# COM-Radio-UHF.net
KiCad netlist of a schematic drawn in Altium Designer
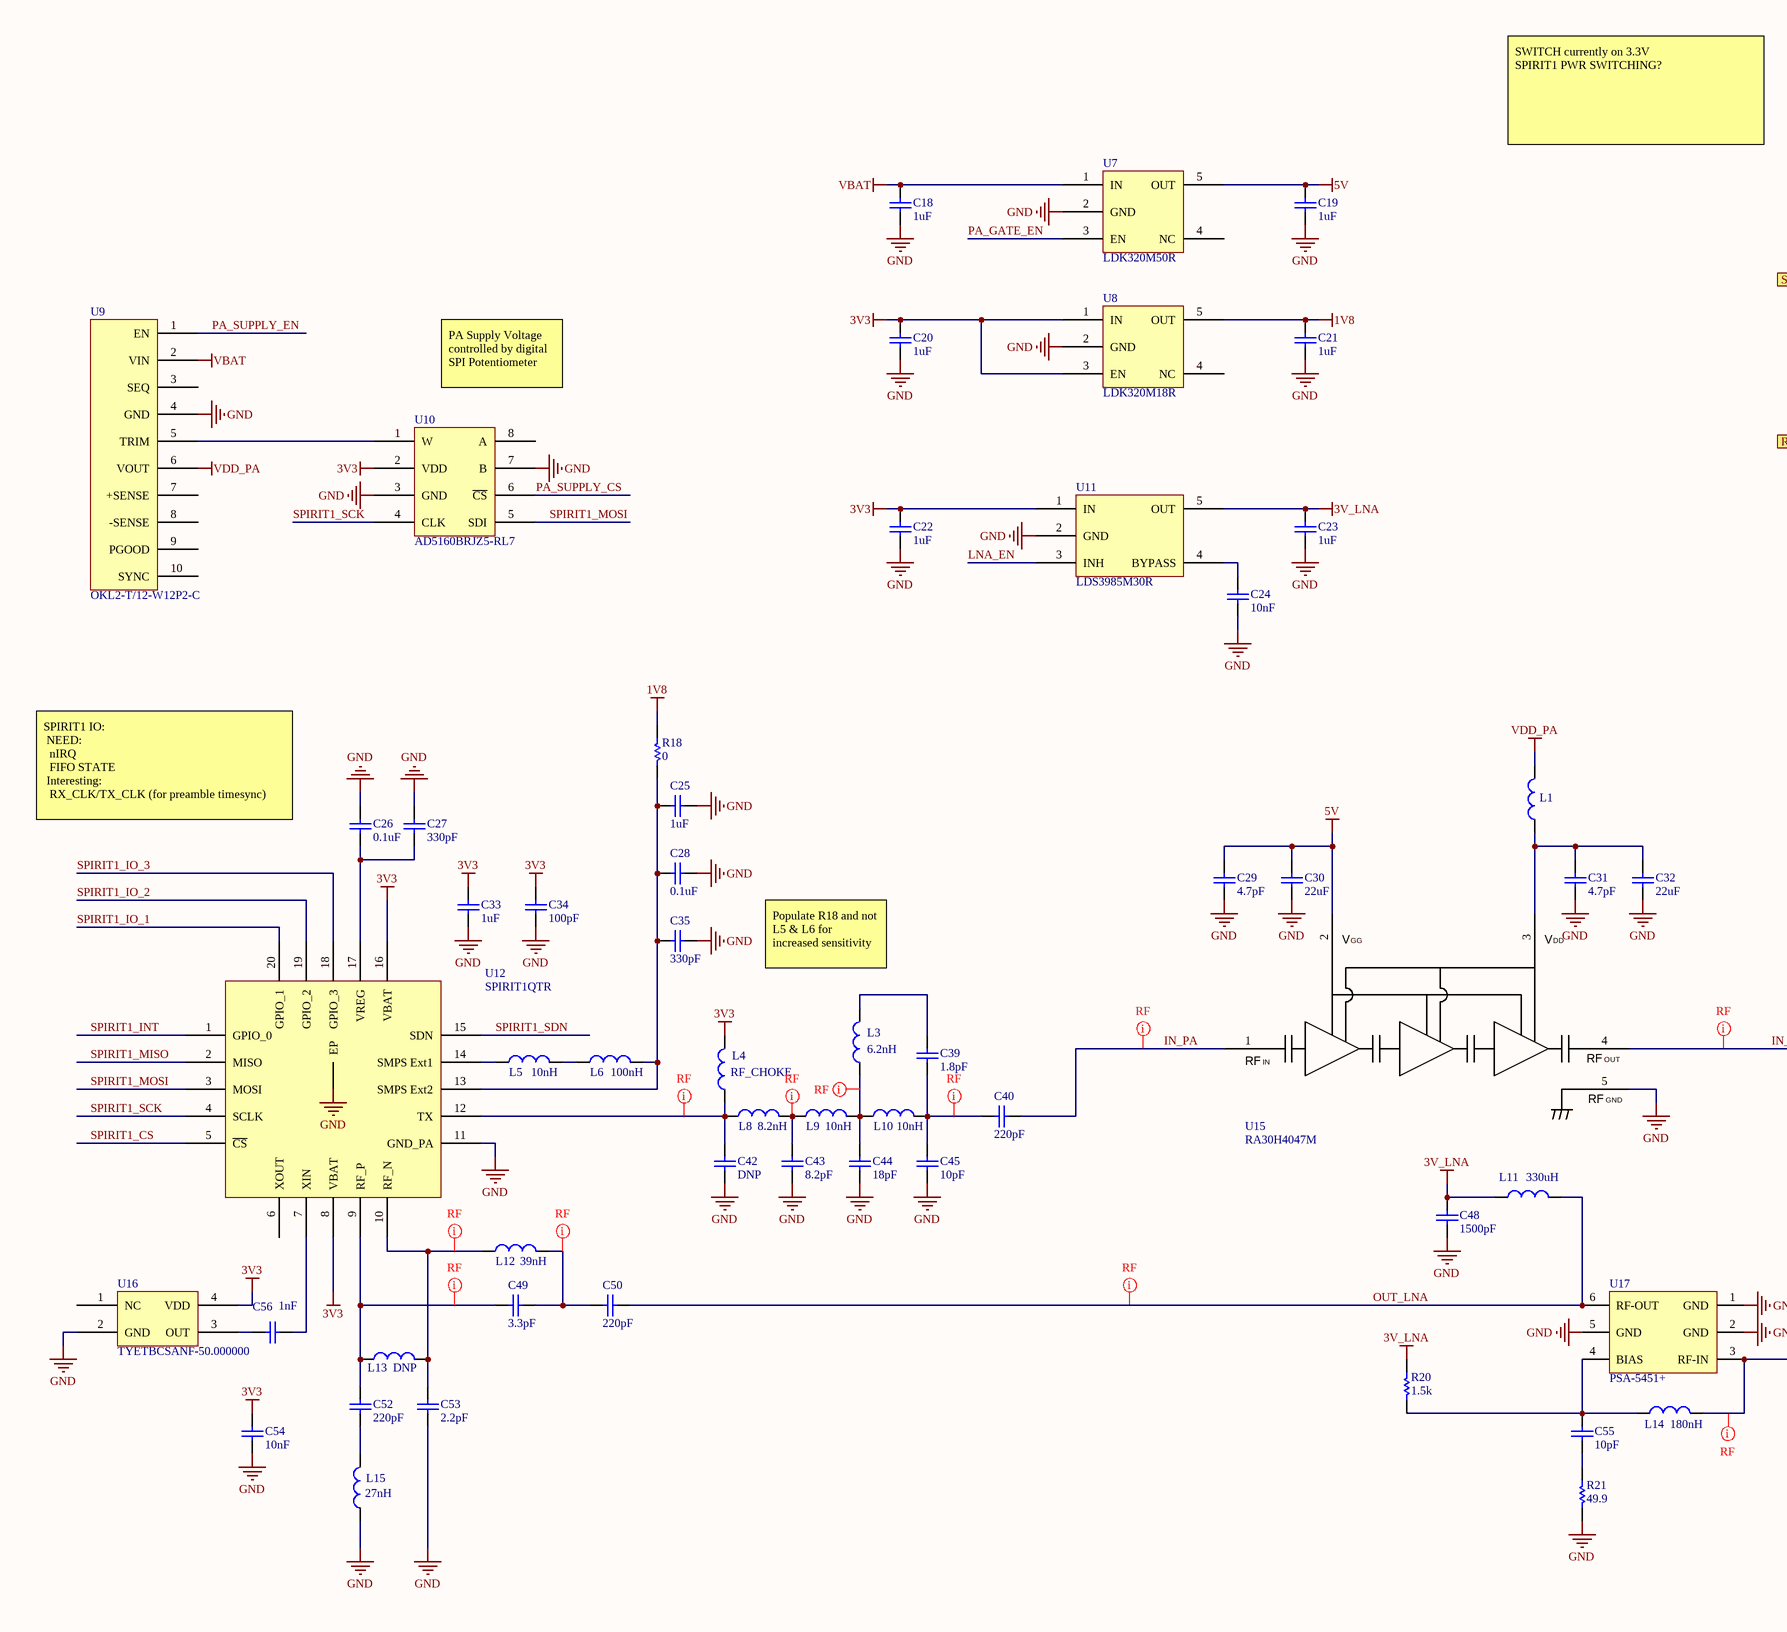
[diagram p0: COM-Radio-UHF.SchDoc, left]
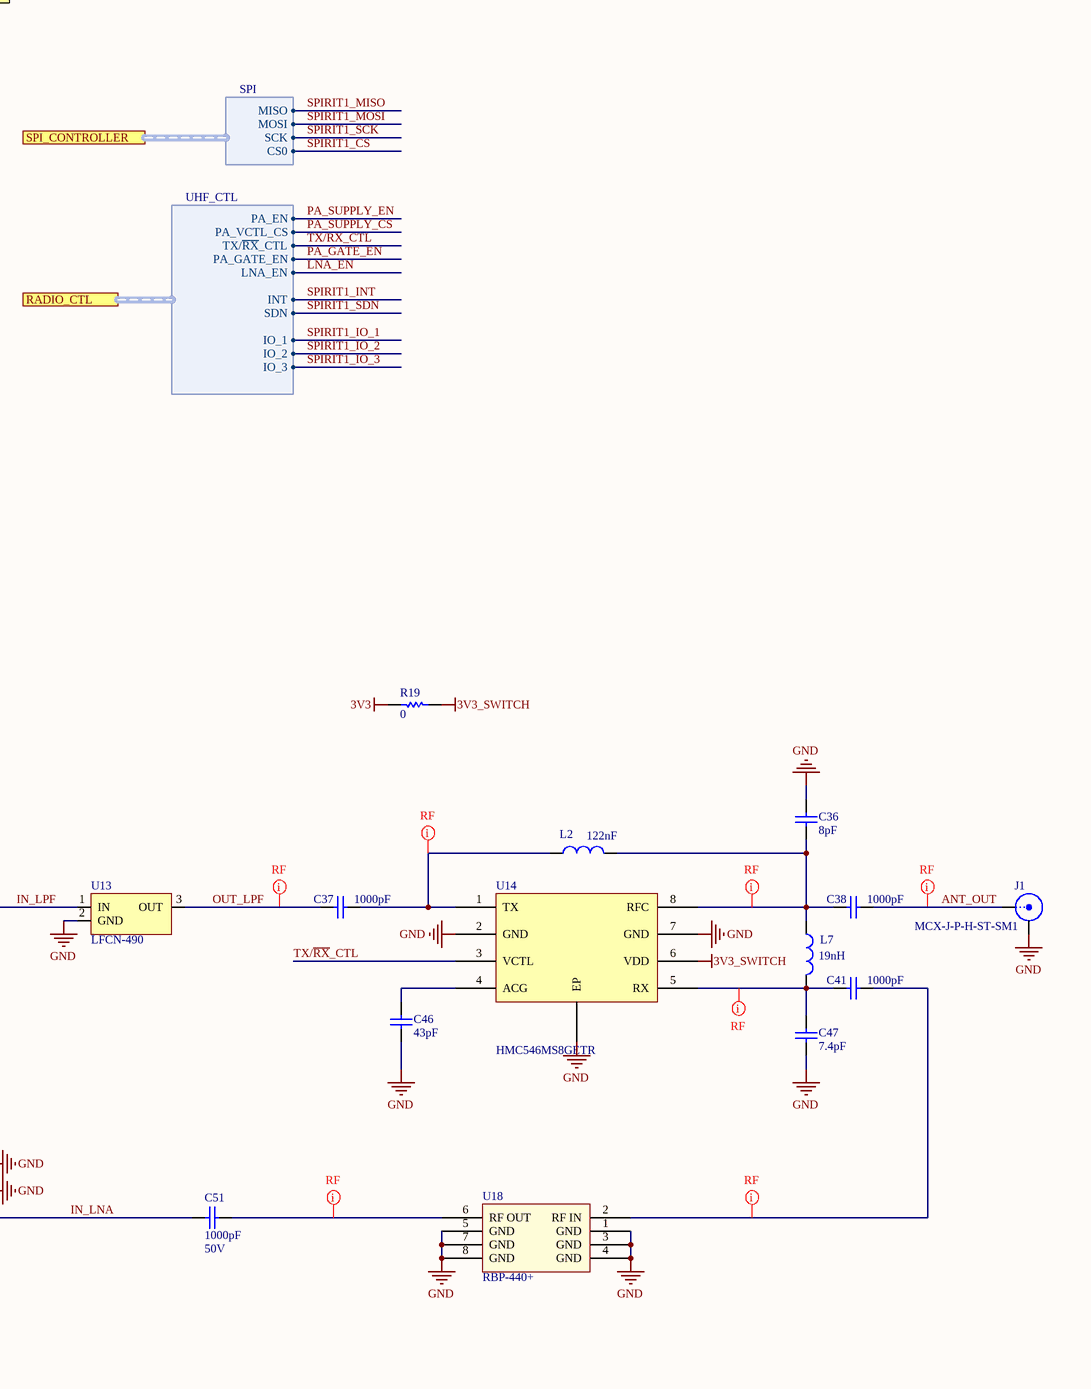
[diagram p1: COM-Radio-UHF.SchDoc, right]

(export (version "E")
  (design (tool "Eeschema 10.0.6"))
  (components
    (comp (ref "C18")
      (value "CL10B105MO8NNWC")
      (footprint "1608[0603]")
      (description "CAP CER 1UF 16V X7R 0603")
      (fields
        (field (name "CAPACITANCE") "1uF")
        (field (name "PARTNUMBER") "CGA2B2X7R1H102M050BA")
        (field (name "MANUFACTURER") "TDK")
      )
      (libsource (lib "PolarCube") (part "Cap"))
    )
    (comp (ref "C19")
      (value "CL10B105MO8NNWC")
      (footprint "1608[0603]")
      (description "CAP CER 1UF 16V X7R 0603")
      (fields
        (field (name "CAPACITANCE") "1uF")
        (field (name "PARTNUMBER") "CGA2B2X7R1H102M050BA")
        (field (name "MANUFACTURER") "TDK")
      )
      (libsource (lib "PolarCube") (part "Cap"))
    )
    (comp (ref "C20")
      (value "CL10B105MO8NNWC")
      (footprint "1608[0603]")
      (description "CAP CER 1UF 16V X7R 0603")
      (fields
        (field (name "CAPACITANCE") "1uF")
        (field (name "PARTNUMBER") "CGA2B2X7R1H102M050BA")
        (field (name "MANUFACTURER") "TDK")
      )
      (libsource (lib "PolarCube") (part "Cap"))
    )
    (comp (ref "C21")
      (value "CL10B105MO8NNWC")
      (footprint "1608[0603]")
      (description "CAP CER 1UF 16V X7R 0603")
      (fields
        (field (name "CAPACITANCE") "1uF")
        (field (name "PARTNUMBER") "CGA2B2X7R1H102M050BA")
        (field (name "MANUFACTURER") "TDK")
      )
      (libsource (lib "PolarCube") (part "Cap"))
    )
    (comp (ref "C22")
      (value "CL10B105MO8NNWC")
      (footprint "1608[0603]")
      (description "CAP CER 1UF 16V X7R 0603")
      (fields
        (field (name "CAPACITANCE") "1uF")
        (field (name "PARTNUMBER") "CGA2B2X7R1H102M050BA")
        (field (name "MANUFACTURER") "TDK")
      )
      (libsource (lib "PolarCube") (part "Cap"))
    )
    (comp (ref "C23")
      (value "CL10B105MO8NNWC")
      (footprint "1608[0603]")
      (description "CAP CER 1UF 16V X7R 0603")
      (fields
        (field (name "CAPACITANCE") "1uF")
        (field (name "PARTNUMBER") "CGA2B2X7R1H102M050BA")
        (field (name "MANUFACTURER") "TDK")
      )
      (libsource (lib "PolarCube") (part "Cap"))
    )
    (comp (ref "C24")
      (value "CL10B103KO8NNNC")
      (footprint "1608[0603]")
      (description "CAP CER 10000PF 16V X7R 0603")
      (fields
        (field (name "CAPACITANCE") "10nF")
        (field (name "PARTNUMBER") "CGA2B2X7R1H102M050BA")
        (field (name "MANUFACTURER") "TDK")
      )
      (libsource (lib "PolarCube") (part "Cap"))
    )
    (comp (ref "C25")
      (value "CL10B105MO8NNWC")
      (footprint "1608[0603]")
      (description "CAP CER 1UF 16V X7R 0603")
      (fields
        (field (name "CAPACITANCE") "1uF")
        (field (name "PARTNUMBER") "CBR04C100J5GAC")
        (field (name "MANUFACTURER") "Kemet")
      )
      (libsource (lib "PolarCube") (part "Cap"))
    )
    (comp (ref "C26")
      (value "CL10B104KB8ZW6C")
      (footprint "1608[0603]")
      (description "MLCC 1608(0603) X7R 100NF 10% 50")
      (fields
        (field (name "CAPACITANCE") "0.1uF")
        (field (name "PARTNUMBER") "CBR04C100J5GAC")
        (field (name "MANUFACTURER") "Kemet")
      )
      (libsource (lib "PolarCube") (part "Cap"))
    )
    (comp (ref "C27")
      (value "CL10C331JB8NFNC")
      (footprint "1608[0603]")
      (description "CAP CER 330PF 50V C0G/NP0 0603")
      (fields
        (field (name "CAPACITANCE") "330pF")
        (field (name "PARTNUMBER") "CBR04C100J5GAC")
        (field (name "MANUFACTURER") "Kemet")
      )
      (libsource (lib "PolarCube") (part "Cap"))
    )
    (comp (ref "C28")
      (value "CL10B104KB8ZW6C")
      (footprint "1608[0603]")
      (description "MLCC 1608(0603) X7R 100NF 10% 50")
      (fields
        (field (name "CAPACITANCE") "0.1uF")
        (field (name "PARTNUMBER") "CBR04C100J5GAC")
        (field (name "MANUFACTURER") "Kemet")
      )
      (libsource (lib "PolarCube") (part "Cap"))
    )
    (comp (ref "C29")
      (value "CL10C4R7BB8NNNC")
      (footprint "1608[0603]")
      (description "CAP CER 4.7PF 50V C0G/NP0 0603")
      (fields
        (field (name "CAPACITANCE") "4.7pF")
        (field (name "PARTNUMBER") "CGA2B2X7R1H102M050BA")
        (field (name "MANUFACTURER") "TDK")
      )
      (libsource (lib "PolarCube") (part "Cap"))
    )
    (comp (ref "C30")
      (value "C3225X5R1C226M250AA")
      (footprint "C1210_M")
      (description "CAP CER 22UF 16V X5R 1210")
      (fields
        (field (name "CAPACITANCE") "22uF")
        (field (name "PARTNUMBER") "CGA2B2X7R1H102M050BA")
        (field (name "MANUFACTURER") "TDK")
      )
      (libsource (lib "PolarCube") (part "Cap"))
    )
    (comp (ref "C31")
      (value "CL10C4R7BB8NNNC")
      (footprint "1608[0603]")
      (description "CAP CER 4.7PF 50V C0G/NP0 0603")
      (fields
        (field (name "CAPACITANCE") "4.7pF")
        (field (name "PARTNUMBER") "CGA2B2X7R1H102M050BA")
        (field (name "MANUFACTURER") "TDK")
      )
      (libsource (lib "PolarCube") (part "Cap"))
    )
    (comp (ref "C32")
      (value "C3225X5R1C226M250AA")
      (footprint "C1210_M")
      (description "CAP CER 22UF 16V X5R 1210")
      (fields
        (field (name "CAPACITANCE") "22uF")
        (field (name "PARTNUMBER") "CGA2B2X7R1H102M050BA")
        (field (name "MANUFACTURER") "TDK")
      )
      (libsource (lib "PolarCube") (part "Cap"))
    )
    (comp (ref "C33")
      (value "CL10B105MO8NNWC")
      (footprint "1608[0603]")
      (description "CAP CER 1UF 16V X7R 0603")
      (fields
        (field (name "CAPACITANCE") "1uF")
        (field (name "PARTNUMBER") "CBR04C100J5GAC")
        (field (name "MANUFACTURER") "Kemet")
      )
      (libsource (lib "PolarCube") (part "Cap"))
    )
    (comp (ref "C34")
      (value "C0603C101K5GACTU")
      (footprint "1608[0603]")
      (description "CAP CER 100PF 50V C0G/NP0 0603")
      (fields
        (field (name "CAPACITANCE") "100pF")
        (field (name "PARTNUMBER") "CBR04C100J5GAC")
        (field (name "MANUFACTURER") "Kemet")
      )
      (libsource (lib "PolarCube") (part "Cap"))
    )
    (comp (ref "C35")
      (value "CL10B331JB8NNNC")
      (footprint "1608[0603]")
      (description "CAP CER 330PF 50V X7R 0603")
      (fields
        (field (name "CAPACITANCE") "330pF")
        (field (name "PARTNUMBER") "CBR04C100J5GAC")
        (field (name "MANUFACTURER") "Kemet")
      )
      (libsource (lib "PolarCube") (part "Cap"))
    )
    (comp (ref "C36")
      (value "CL10C080CB8NNNC")
      (footprint "1608[0603]")
      (description "CAP CER 8PF 50V C0G/NP0 0603")
      (fields
        (field (name "CAPACITANCE") "8pF")
        (field (name "PARTNUMBER") "CGA2B2X7R1H102M050BA")
        (field (name "MANUFACTURER") "TDK")
      )
      (libsource (lib "PolarCube") (part "Cap"))
    )
    (comp (ref "C37")
      (value "C0603X102J5GAC7867")
      (footprint "1608[0603]")
      (description "CAP CER 1000PF 50V C0G/NP0 0603")
      (fields
        (field (name "CAPACITANCE") "1000pF")
        (field (name "PARTNUMBER") "CGA2B2X7R1H102M050BA")
        (field (name "MANUFACTURER") "TDK")
      )
      (libsource (lib "PolarCube") (part "Cap"))
    )
    (comp (ref "C38")
      (value "C0603X102J5GAC7867")
      (footprint "1608[0603]")
      (description "CAP CER 1000PF 50V C0G/NP0 0603")
      (fields
        (field (name "CAPACITANCE") "1000pF")
        (field (name "PARTNUMBER") "CGA2B2X7R1H102M050BA")
        (field (name "MANUFACTURER") "TDK")
      )
      (libsource (lib "PolarCube") (part "Cap"))
    )
    (comp (ref "C39")
      (value "CL10C1R8BB8NNNC")
      (footprint "1608[0603]")
      (description "CAP CER 1.8PF 50V C0G/NP0 0603")
      (fields
        (field (name "CAPACITANCE") "1.8pF")
        (field (name "PARTNUMBER") "CBR04C100J5GAC")
        (field (name "MANUFACTURER") "Kemet")
      )
      (libsource (lib "PolarCube") (part "Cap"))
    )
    (comp (ref "C40")
      (value "CL10C221JB8NNNC")
      (footprint "1608[0603]")
      (description "CAP CER 220PF 50V C0G/NP0 0603")
      (fields
        (field (name "CAPACITANCE") "220pF")
        (field (name "PARTNUMBER") "CBR04C100J5GAC")
        (field (name "MANUFACTURER") "Kemet")
      )
      (libsource (lib "PolarCube") (part "Cap"))
    )
    (comp (ref "C41")
      (value "C0603X102J5GAC7867")
      (footprint "1608[0603]")
      (description "CAP CER 1000PF 50V C0G/NP0 0603")
      (fields
        (field (name "CAPACITANCE") "1000pF")
        (field (name "PARTNUMBER") "CGA2B2X7R1H102M050BA")
        (field (name "MANUFACTURER") "TDK")
      )
      (libsource (lib "PolarCube") (part "Cap"))
    )
    (comp (ref "C42")
      (value "Cap")
      (footprint "1608[0603]")
      (description "RF Microwave MLCCs")
      (fields
        (field (name "CAPACITANCE") "DNP")
        (field (name "PARTNUMBER") "CBR04C100J5GAC")
        (field (name "MANUFACTURER") "Kemet")
      )
      (libsource (lib "PolarCube") (part "Cap"))
    )
    (comp (ref "C43")
      (value "CL10C8R2DB8NNNC")
      (footprint "1608[0603]")
      (description "CAP CER 8.2PF 50V C0G/NP0 0603")
      (fields
        (field (name "CAPACITANCE") "8.2pF")
        (field (name "PARTNUMBER") "CBR04C100J5GAC")
        (field (name "MANUFACTURER") "Kemet")
      )
      (libsource (lib "PolarCube") (part "Cap"))
    )
    (comp (ref "C44")
      (value "C0603C180K5GACTU")
      (footprint "1608[0603]")
      (description "CAP CER 18PF 50V C0G/NP0 0603")
      (fields
        (field (name "CAPACITANCE") "18pF")
        (field (name "PARTNUMBER") "CBR04C100J5GAC")
        (field (name "MANUFACTURER") "Kemet")
      )
      (libsource (lib "PolarCube") (part "Cap"))
    )
    (comp (ref "C45")
      (value "CL10C100JB8NCNC")
      (footprint "1608[0603]")
      (description "CAP CER 10PF 50V C0G/NP0 0603")
      (fields
        (field (name "CAPACITANCE") "10pF")
        (field (name "PARTNUMBER") "CBR04C100J5GAC")
        (field (name "MANUFACTURER") "Kemet")
      )
      (libsource (lib "PolarCube") (part "Cap"))
    )
    (comp (ref "C46")
      (value "C0603C430J5GACTU")
      (footprint "1608[0603]")
      (description "CAP CER 43PF 50V C0G/NP0 0603")
      (fields
        (field (name "CAPACITANCE") "43pF")
        (field (name "PARTNUMBER") "CGA2B2X7R1H102M050BA")
        (field (name "MANUFACTURER") "TDK")
      )
      (libsource (lib "PolarCube") (part "Cap"))
    )
    (comp (ref "C47")
      (value "CBR06C749B5GAC")
      (footprint "1608[0603]")
      (description "CAP CER RF 7.4PF 50V +/-0.1 PF C")
      (fields
        (field (name "CAPACITANCE") "7.4pF")
        (field (name "PARTNUMBER") "CGA2B2X7R1H102M050BA")
        (field (name "MANUFACTURER") "TDK")
      )
      (libsource (lib "PolarCube") (part "Cap"))
    )
    (comp (ref "C48")
      (value "C0603C152J5GACTU")
      (footprint "1608[0603]")
      (description "CAP CER 1500PF 50V C0G/NP0 0603")
      (fields
        (field (name "CAPACITANCE") "1500pF")
        (field (name "PARTNUMBER") "CGA2B2X7R1H102M050BA")
        (field (name "MANUFACTURER") "TDK")
      )
      (libsource (lib "PolarCube") (part "Cap"))
    )
    (comp (ref "C49")
      (value "06035A3R3BAT2A")
      (footprint "1608[0603]")
      (description "CAP CER 3.3PF 50V C0G/NP0 0603")
      (fields
        (field (name "CAPACITANCE") "3.3pF")
        (field (name "PARTNUMBER") "CBR04C100J5GAC")
        (field (name "MANUFACTURER") "Kemet")
      )
      (libsource (lib "PolarCube") (part "Cap"))
    )
    (comp (ref "C50")
      (value "CL10C221JB8NNNC")
      (footprint "1608[0603]")
      (description "CAP CER 220PF 50V C0G/NP0 0603")
      (fields
        (field (name "CAPACITANCE") "220pF")
        (field (name "PARTNUMBER") "CBR04C100J5GAC")
        (field (name "MANUFACTURER") "Kemet")
      )
      (libsource (lib "PolarCube") (part "Cap"))
    )
    (comp (ref "C51")
      (value "C0603X102J5GAC7867")
      (footprint "1608[0603]")
      (description "CAP CER 1000PF 50V C0G/NP0 0603")
      (fields
        (field (name "CAPACITANCE") "1000pF")
        (field (name "VOLTAGE") "50V")
        (field (name "PARTNUMBER") "CGA2B2X7R1H102M050BA")
        (field (name "MANUFACTURER") "TDK")
      )
      (libsource (lib "PolarCube") (part "Cap"))
    )
    (comp (ref "C52")
      (value "CL10C221JB8NNNC")
      (footprint "1608[0603]")
      (description "CAP CER 220PF 50V C0G/NP0 0603")
      (fields
        (field (name "CAPACITANCE") "220pF")
        (field (name "PARTNUMBER") "CBR04C100J5GAC")
        (field (name "MANUFACTURER") "Kemet")
      )
      (libsource (lib "PolarCube") (part "Cap"))
    )
    (comp (ref "C53")
      (value "C0603C229B5GAC7867")
      (footprint "1608[0603]")
      (description "CAP CER 2.2PF 50V NP0 0603")
      (fields
        (field (name "CAPACITANCE") "2.2pF")
        (field (name "PARTNUMBER") "CBR04C100J5GAC")
        (field (name "MANUFACTURER") "Kemet")
      )
      (libsource (lib "PolarCube") (part "Cap"))
    )
    (comp (ref "C54")
      (value "Cap")
      (footprint "1608[0603]")
      (description "RF Microwave MLCCs")
      (fields
        (field (name "CAPACITANCE") "10nF")
        (field (name "PARTNUMBER") "CBR04C100J5GAC")
        (field (name "MANUFACTURER") "Kemet")
      )
      (libsource (lib "PolarCube") (part "Cap"))
    )
    (comp (ref "C55")
      (value "CL10C100JB8NCNC")
      (footprint "1608[0603]")
      (description "CAP CER 10PF 50V C0G/NP0 0603")
      (fields
        (field (name "CAPACITANCE") "10pF")
        (field (name "PARTNUMBER") "CBR04C100J5GAC")
        (field (name "MANUFACTURER") "Kemet")
      )
      (libsource (lib "PolarCube") (part "Cap"))
    )
    (comp (ref "C56")
      (value "CL10B102KA8NNNC")
      (footprint "1608[0603]")
      (description "CAP CER 1000PF 25V X7R 0603")
      (fields
        (field (name "CAPACITANCE") "1nF")
        (field (name "PARTNUMBER") "CBR04C100J5GAC")
        (field (name "MANUFACTURER") "Kemet")
      )
      (libsource (lib "PolarCube") (part "Cap"))
    )
    (comp (ref "J1")
      (value "MCX-J-P-H-ST-SM1")
      (footprint "MCX-J-P-H-ST-SM1")
      (description "MCX Connector Jack, Female Socket 50 Ohm Surface Mount Solder")
      (fields (field (name "PARTNUMBER") "MMCX-J-P-H-RA-TH1"))
      (libsource (lib "UHF-schlib") (part "MMCX-J-P-H-RA-TH1"))
    )
    (comp (ref "L1")
      (value "SDR2207-4R7ML")
      (footprint "SDR2207-4R7ML")
      (description "FIXED IND 4.7UH 8.5A 8.8 MOHM")
      (fields (field (name "PARTNUMBER") "MLG1005SR18JT000") (field (name "MANUFACTURER") "TDK"))
      (libsource (lib "PolarCube") (part "Inductor"))
    )
    (comp (ref "L2")
      (value "PE-0603CD121GTT")
      (footprint "1608[0603]")
      (description "FIXED IND 122NH 300MA 650 MOHM")
      (fields
        (field (name "INDUCTANCE") "122nF")
        (field (name "PARTNUMBER") "MLG1005SR18JT000")
        (field (name "MANUFACTURER") "TDK")
      )
      (libsource (lib "PolarCube") (part "Inductor"))
    )
    (comp (ref "L3")
      (value "LQG18HH6N2S00D")
      (footprint "1608[0603]")
      (description "FIXED IND 6.2NH 430MA 200 MOHM")
      (fields
        (field (name "INDUCTANCE") "6.2nH")
        (field (name "PARTNUMBER") "MLG1005SR18JT000")
        (field (name "MANUFACTURER") "TDK")
      )
      (libsource (lib "PolarCube") (part "Inductor"))
    )
    (comp (ref "L4")
      (value "LQM21FN100M80L")
      (footprint "6-0805_M")
      (description "FIXED IND 10UH 100MA 300 MOHM")
      (fields
        (field (name "PARTNUMBER") "MLG1005SR18JT000")
        (field (name "MANUFACTURER") "TDK")
        (field (name "TYPE") "RF_CHOKE")
      )
      (libsource (lib "PolarCube") (part "Inductor"))
    )
    (comp (ref "L5")
      (value "L-14C10NJV4T")
      (footprint "1608[0603]")
      (description "FIXED IND 10NH 300MA 350 MOHM")
      (fields
        (field (name "INDUCTANCE") "10nH")
        (field (name "PARTNUMBER") "MLG1005SR18JT000")
        (field (name "MANUFACTURER") "TDK")
      )
      (libsource (lib "PolarCube") (part "Inductor"))
    )
    (comp (ref "L6")
      (value "HK1608R10J-T")
      (footprint "1608[0603]")
      (description "FIXED IND 100NH 300MA 100 MOHM")
      (fields
        (field (name "INDUCTANCE") "100nH")
        (field (name "PARTNUMBER") "MLG1005SR18JT000")
        (field (name "MANUFACTURER") "TDK")
      )
      (libsource (lib "PolarCube") (part "Inductor"))
    )
    (comp (ref "L7")
      (value "LQW18AN19NJ8ZD")
      (footprint "1608[0603]")
      (description "FIXED IND 19NH 1.4A 75 MOHM")
      (fields
        (field (name "INDUCTANCE") "19nH")
        (field (name "PARTNUMBER") "MLG1005SR18JT000")
        (field (name "MANUFACTURER") "TDK")
      )
      (libsource (lib "PolarCube") (part "Inductor"))
    )
    (comp (ref "L8")
      (value "L-14C8N2JV4T")
      (footprint "1608[0603]")
      (description "FIXED IND 8.2NH 300MA 330 MOHM")
      (fields
        (field (name "INDUCTANCE") "8.2nH")
        (field (name "PARTNUMBER") "MLG1005SR18JT000")
        (field (name "MANUFACTURER") "TDK")
      )
      (libsource (lib "PolarCube") (part "Inductor"))
    )
    (comp (ref "L9")
      (value "L-14C10NJV4T")
      (footprint "1608[0603]")
      (description "FIXED IND 10NH 300MA 350 MOHM")
      (fields
        (field (name "INDUCTANCE") "10nH")
        (field (name "PARTNUMBER") "MLG1005SR18JT000")
        (field (name "MANUFACTURER") "TDK")
      )
      (libsource (lib "PolarCube") (part "Inductor"))
    )
    (comp (ref "L10")
      (value "L-14C10NJV4T")
      (footprint "1608[0603]")
      (description "FIXED IND 10NH 300MA 350 MOHM")
      (fields
        (field (name "INDUCTANCE") "10nH")
        (field (name "PARTNUMBER") "MLG1005SR18JT000")
        (field (name "MANUFACTURER") "TDK")
      )
      (libsource (lib "PolarCube") (part "Inductor"))
    )
    (comp (ref "L11")
      (value "SRR7045-331M")
      (footprint "1608[0603]")
      (description "FIXED IND 330UH 400MA 730 MOHM")
      (fields
        (field (name "INDUCTANCE") "330uH")
        (field (name "PARTNUMBER") "MLG1005SR18JT000")
        (field (name "MANUFACTURER") "TDK")
      )
      (libsource (lib "PolarCube") (part "Inductor"))
    )
    (comp (ref "L12")
      (value "L-14C39NJV4T")
      (footprint "1608[0603]")
      (description "FIXED IND 39NH 300MA 700 MOHM")
      (fields
        (field (name "INDUCTANCE") "39nH")
        (field (name "PARTNUMBER") "MLG1005SR18JT000")
        (field (name "MANUFACTURER") "TDK")
      )
      (libsource (lib "PolarCube") (part "Inductor"))
    )
    (comp (ref "L13")
      (value "DNP")
      (footprint "1608[0603]")
      (fields (field (name "PARTNUMBER") "MLG1005SR18JT000") (field (name "MANUFACTURER") "TDK"))
      (libsource (lib "PolarCube") (part "Inductor"))
    )
    (comp (ref "L14")
      (value "CIH10TR18JNC")
      (footprint "1608[0603]")
      (description "FIXED IND 180NH 250MA 1.3 OHM")
      (fields
        (field (name "INDUCTANCE") "180nH")
        (field (name "PARTNUMBER") "MLG1005SR18JT000")
        (field (name "MANUFACTURER") "TDK")
      )
      (libsource (lib "PolarCube") (part "Inductor"))
    )
    (comp (ref "L15")
      (value "L-14C27NJV4T")
      (footprint "1608[0603]")
      (description "FIXED IND 27NH 300MA 600 MOHM")
      (fields
        (field (name "INDUCTANCE") "27nH")
        (field (name "PARTNUMBER") "MLG1005SR18JT000")
        (field (name "MANUFACTURER") "TDK")
      )
      (libsource (lib "PolarCube") (part "Inductor"))
    )
    (comp (ref "R18")
      (value "CRCW06030000Z0EAC")
      (footprint "1608[0603]")
      (description "RES SMD 0 OHM JUMP 1/10W 0603")
      (fields
        (field (name "RESISTANCE") "0")
        (field (name "PARTNUMBER") "CRCW040249R9FKED")
        (field (name "MANUFACTURER") "Vishay")
      )
      (libsource (lib "PolarCube") (part "Res"))
    )
    (comp (ref "R19")
      (value "CRCW06030000Z0EAC")
      (footprint "1608[0603]")
      (description "RES SMD 0 OHM JUMP 1/10W 0603")
      (fields
        (field (name "RESISTANCE") "0")
        (field (name "PARTNUMBER") "CRCW04021K50FKED")
        (field (name "MANUFACTURER") "Vishay")
      )
      (libsource (lib "PolarCube") (part "Res"))
    )
    (comp (ref "R20")
      (value "CRG0603F1K5")
      (footprint "1608[0603]")
      (description "RES SMD 1.5K OHM 1% 1/10W 0603")
      (fields
        (field (name "RESISTANCE") "1.5k")
        (field (name "PARTNUMBER") "CRCW04021K50FKED")
        (field (name "MANUFACTURER") "Vishay")
      )
      (libsource (lib "PolarCube") (part "Res"))
    )
    (comp (ref "R21")
      (value "ERJ-3EKF49R9V")
      (footprint "1608[0603]")
      (description "RES SMD 49.9 OHM 1% 1/10W 0603")
      (fields
        (field (name "RESISTANCE") "49.9")
        (field (name "PARTNUMBER") "CRCW040249R9FKED")
        (field (name "MANUFACTURER") "Vishay")
      )
      (libsource (lib "PolarCube") (part "Res"))
    )
    (comp (ref "U7")
      (value "LDK320M50R")
      (footprint "SOT95P280X145-5N")
      (description "Linear Voltage Regulator IC Positive Fixed 1 Output 5V 200mA SOT-23-5")
      (libsource (lib "Cesium_3") (part "LDK320M50R"))
    )
    (comp (ref "U8")
      (value "LDK320M18R")
      (footprint "SOT95P280X145-5N")
      (description "Linear Voltage Regulator IC Positive Fixed 1 Output 1.8V 200mA SOT-23-5")
      (libsource (lib "Cesium_3") (part "LDK320M18R"))
    )
    (comp (ref "U9")
      (value "OKL2-T/12-W12P2-C")
      (footprint "OKL2-T/12-W12P2-C")
      (description "Non-Isolated PoL Module DC DC Converter 1 Output 0.69 ~ 5.5 V 12A 4.5V - 14V Input")
      (libsource (lib "Cesium_3") (part "OKL2-T/12-W12P2-C"))
    )
    (comp (ref "U10")
      (value "AD5160BRJZ5-RL7")
      (footprint "TSOP65P280X130-8N")
      (description "Digital Potentiometer 5k Ohm 1 Circuit 256 Taps SPI Interface SOT-23-8")
      (libsource (lib "Cesium_3") (part "AD5160BRJZ5-RL7"))
    )
    (comp (ref "U11")
      (value "LDS3985M30R")
      (footprint "SOT95P280X145-5N")
      (description "Linear Voltage Regulator IC Positive Fixed 1 Output 3V 300mA SOT-23-5")
      (libsource (lib "Cesium_3") (part "LDS3985M30R"))
    )
    (comp (ref "U12")
      (value "SPIRIT1QTR")
      (footprint "QFN50P400X400X100_HS-21N")
      (libsource (lib "Cesium_3") (part "SPIRIT1QTR"))
    )
    (comp (ref "U13")
      (value "LFCN-490")
      (footprint "LFCN-490")
      (description "Low Pass Filter with knee at 490MHz")
      (fields (field (name "MANUFACTURER") "Mini Circuits"))
      (libsource (lib "PolarCube") (part "LFCN-490"))
    )
    (comp (ref "U14")
      (value "HMC546MS8GETR")
      (footprint "TSOP65P490X110_HS-9N")
      (description "RF Switch IC Cellular SPDT 2.2GHz 50 Ohm 8-MSOP")
      (libsource (lib "Cesium_3") (part "HMC546MS8GETR"))
    )
    (comp (ref "U15")
      (value "RA30H4047M")
      (footprint "RA30H4047M_BRD_MNT")
      (libsource (lib "Cesium_3") (part "RA30H4047M"))
    )
    (comp (ref "U16")
      (value "TYETBCSANF-50.000000")
      (footprint "TYETBCSANF")
      (description "50MHz TCXO Clipped Sine Wave Oscillator 2.8 V ~ 3.3 V 4-SMD, No Lead")
      (libsource (lib "Cesium_3") (part "TYETBCSANF-50.000000"))
    )
    (comp (ref "U17")
      (value "PSA-5451+")
      (footprint "SOT65P215X100-6N")
      (description "LNA, DC-4GHz, 29dBm IP3")
      (fields (field (name "MANUFACTURER") "Mini Circuits"))
      (libsource (lib "PolarCube") (part "PSA-5451+"))
    )
    (comp (ref "U18")
      (value "RBP-440+")
      (footprint "RBP-440+")
      (description "RF Filter,0.5W")
      (fields (field (name "MANUFACTURER") "Mini Circuits"))
      (libsource (lib "PolarCube") (part "RBP-440+"))
    )
  )
  (nets
    (net (code "3") (name "/ANT_OUT") (class "Default")
      (node (ref "C38") (pin "2") (pinfunction "2_2") (pintype "passive"))
      (node (ref "J1") (pin "1") (pinfunction "1_1") (pintype "passive"))
    )
    (net (code "4") (name "/IN_LNA") (class "Default")
      (node (ref "C51") (pin "2") (pinfunction "2_2") (pintype "passive"))
      (node (ref "L14") (pin "1") (pinfunction "1_1") (pintype "passive"))
      (node (ref "U17") (pin "3") (pinfunction "RF-IN_3") (pintype "passive"))
    )
    (net (code "5") (name "/IN_LPF") (class "Default")
      (node (ref "U13") (pin "1") (pinfunction "IN_1") (pintype "passive"))
      (node (ref "U15") (pin "4") (pinfunction "POUT_4") (pintype "passive"))
    )
    (net (code "6") (name "/IN_PA") (class "Default")
      (node (ref "C40") (pin "1") (pinfunction "1_1") (pintype "passive"))
      (node (ref "U15") (pin "1") (pinfunction "PIN_1") (pintype "passive"))
    )
    (net (code "7") (name "/LNA_EN") (class "Default")
      (node (ref "U11") (pin "3") (pinfunction "INH_3") (pintype "passive"))
    )
    (net (code "8") (name "/OUT_LNA") (class "Default")
      (node (ref "C50") (pin "1") (pinfunction "1_1") (pintype "passive"))
      (node (ref "L11") (pin "1") (pinfunction "1_1") (pintype "passive"))
      (node (ref "U17") (pin "6") (pinfunction "RF-OUT_6") (pintype "passive"))
    )
    (net (code "9") (name "/OUT_LPF") (class "Default")
      (node (ref "C37") (pin "1") (pinfunction "1_1") (pintype "passive"))
      (node (ref "U13") (pin "3") (pinfunction "OUT_3") (pintype "passive"))
    )
    (net (code "10") (name "/PA_GATE_EN") (class "Default")
      (node (ref "U7") (pin "3") (pinfunction "EN_3") (pintype "passive"))
    )
    (net (code "11") (name "/PA_SUPPLY_CS") (class "Default")
      (node (ref "U10") (pin "6") (pinfunction "~{CS}_6") (pintype "passive"))
    )
    (net (code "12") (name "/PA_SUPPLY_EN") (class "Default")
      (node (ref "U9") (pin "1") (pinfunction "EN_1") (pintype "passive"))
    )
    (net (code "13") (name "/SPIRIT1_CS") (class "Default")
      (node (ref "U12") (pin "5") (pinfunction "~{CS}_5") (pintype "passive"))
    )
    (net (code "14") (name "/SPIRIT1_INT") (class "Default")
      (node (ref "U12") (pin "1") (pinfunction "GPIO_0_1") (pintype "passive"))
    )
    (net (code "15") (name "/SPIRIT1_IO_1") (class "Default")
      (node (ref "U12") (pin "20") (pinfunction "GPIO_1_20") (pintype "passive"))
    )
    (net (code "16") (name "/SPIRIT1_IO_2") (class "Default")
      (node (ref "U12") (pin "19") (pinfunction "GPIO_2_19") (pintype "passive"))
    )
    (net (code "17") (name "/SPIRIT1_IO_3") (class "Default")
      (node (ref "U12") (pin "18") (pinfunction "GPIO_3_18") (pintype "passive"))
    )
    (net (code "18") (name "/SPIRIT1_MISO") (class "Default")
      (node (ref "U12") (pin "2") (pinfunction "MISO_2") (pintype "passive"))
    )
    (net (code "19") (name "/SPIRIT1_MOSI") (class "Default")
      (node (ref "U10") (pin "5") (pinfunction "SDI_5") (pintype "passive"))
      (node (ref "U12") (pin "3") (pinfunction "MOSI_3") (pintype "passive"))
    )
    (net (code "20") (name "/SPIRIT1_SCK") (class "Default")
      (node (ref "U10") (pin "4") (pinfunction "CLK_4") (pintype "passive"))
      (node (ref "U12") (pin "4") (pinfunction "SCLK_4") (pintype "passive"))
    )
    (net (code "21") (name "/SPIRIT1_SDN") (class "Default")
      (node (ref "U12") (pin "15") (pinfunction "SDN_15") (pintype "passive"))
    )
    (net (code "22") (name "/TX{slash}~{RX}_CTL") (class "Default")
      (node (ref "U14") (pin "3") (pinfunction "VCTL_3") (pintype "passive"))
    )
    (net (code "25") (name "1V8") (class "Default")
      (node (ref "C21") (pin "2") (pinfunction "2_2") (pintype "passive"))
      (node (ref "R18") (pin "1") (pinfunction "1_1") (pintype "passive"))
      (node (ref "U8") (pin "5") (pinfunction "OUT_5") (pintype "passive"))
    )
    (net (code "26") (name "3V3") (class "Default")
      (node (ref "C20") (pin "2") (pinfunction "2_2") (pintype "passive"))
      (node (ref "C22") (pin "2") (pinfunction "2_2") (pintype "passive"))
      (node (ref "C33") (pin "2") (pinfunction "2_2") (pintype "passive"))
      (node (ref "C34") (pin "2") (pinfunction "2_2") (pintype "passive"))
      (node (ref "C54") (pin "2") (pinfunction "2_2") (pintype "passive"))
      (node (ref "L4") (pin "1") (pinfunction "1_1") (pintype "passive"))
      (node (ref "R19") (pin "2") (pinfunction "2_2") (pintype "passive"))
      (node (ref "U10") (pin "2") (pinfunction "VDD_2") (pintype "passive"))
      (node (ref "U11") (pin "1") (pinfunction "IN_1") (pintype "passive"))
      (node (ref "U12") (pin "16") (pinfunction "VBAT_16") (pintype "passive"))
      (node (ref "U12") (pin "8") (pinfunction "VBAT_8") (pintype "passive"))
      (node (ref "U16") (pin "4") (pinfunction "VDD_4") (pintype "passive"))
      (node (ref "U8") (pin "1") (pinfunction "IN_1") (pintype "passive"))
      (node (ref "U8") (pin "3") (pinfunction "EN_3") (pintype "passive"))
    )
    (net (code "27") (name "3V3_SWITCH") (class "Default")
      (node (ref "R19") (pin "1") (pinfunction "1_1") (pintype "passive"))
      (node (ref "U14") (pin "6") (pinfunction "VDD_6") (pintype "passive"))
    )
    (net (code "28") (name "3V_LNA") (class "Default")
      (node (ref "C23") (pin "2") (pinfunction "2_2") (pintype "passive"))
      (node (ref "C48") (pin "2") (pinfunction "2_2") (pintype "passive"))
      (node (ref "L11") (pin "2") (pinfunction "2_2") (pintype "passive"))
      (node (ref "R20") (pin "2") (pinfunction "2_2") (pintype "passive"))
      (node (ref "U11") (pin "5") (pinfunction "OUT_5") (pintype "passive"))
    )
    (net (code "29") (name "5V") (class "Default")
      (node (ref "C19") (pin "2") (pinfunction "2_2") (pintype "passive"))
      (node (ref "C29") (pin "2") (pinfunction "2_2") (pintype "passive"))
      (node (ref "C30") (pin "2") (pinfunction "2_2") (pintype "passive"))
      (node (ref "U15") (pin "2") (pinfunction "VGG_2") (pintype "passive"))
      (node (ref "U7") (pin "5") (pinfunction "OUT_5") (pintype "passive"))
    )
    (net (code "30") (name "GND") (class "Default")
      (node (ref "C18") (pin "1") (pinfunction "1_1") (pintype "passive"))
      (node (ref "C19") (pin "1") (pinfunction "1_1") (pintype "passive"))
      (node (ref "C20") (pin "1") (pinfunction "1_1") (pintype "passive"))
      (node (ref "C21") (pin "1") (pinfunction "1_1") (pintype "passive"))
      (node (ref "C22") (pin "1") (pinfunction "1_1") (pintype "passive"))
      (node (ref "C23") (pin "1") (pinfunction "1_1") (pintype "passive"))
      (node (ref "C24") (pin "1") (pinfunction "1_1") (pintype "passive"))
      (node (ref "C25") (pin "1") (pinfunction "1_1") (pintype "passive"))
      (node (ref "C26") (pin "2") (pinfunction "2_2") (pintype "passive"))
      (node (ref "C27") (pin "2") (pinfunction "2_2") (pintype "passive"))
      (node (ref "C28") (pin "1") (pinfunction "1_1") (pintype "passive"))
      (node (ref "C29") (pin "1") (pinfunction "1_1") (pintype "passive"))
      (node (ref "C30") (pin "1") (pinfunction "1_1") (pintype "passive"))
      (node (ref "C31") (pin "1") (pinfunction "1_1") (pintype "passive"))
      (node (ref "C32") (pin "1") (pinfunction "1_1") (pintype "passive"))
      (node (ref "C33") (pin "1") (pinfunction "1_1") (pintype "passive"))
      (node (ref "C34") (pin "1") (pinfunction "1_1") (pintype "passive"))
      (node (ref "C35") (pin "2") (pinfunction "2_2") (pintype "passive"))
      (node (ref "C36") (pin "2") (pinfunction "2_2") (pintype "passive"))
      (node (ref "C42") (pin "1") (pinfunction "1_1") (pintype "passive"))
      (node (ref "C43") (pin "1") (pinfunction "1_1") (pintype "passive"))
      (node (ref "C44") (pin "1") (pinfunction "1_1") (pintype "passive"))
      (node (ref "C45") (pin "1") (pinfunction "1_1") (pintype "passive"))
      (node (ref "C46") (pin "1") (pinfunction "1_1") (pintype "passive"))
      (node (ref "C47") (pin "1") (pinfunction "1_1") (pintype "passive"))
      (node (ref "C48") (pin "1") (pinfunction "1_1") (pintype "passive"))
      (node (ref "C53") (pin "1") (pinfunction "1_1") (pintype "passive"))
      (node (ref "C54") (pin "1") (pinfunction "1_1") (pintype "passive"))
      (node (ref "J1") (pin "2") (pinfunction "2_2") (pintype "passive"))
      (node (ref "L15") (pin "2") (pinfunction "2_2") (pintype "passive"))
      (node (ref "R21") (pin "2") (pinfunction "2_2") (pintype "passive"))
      (node (ref "U10") (pin "3") (pinfunction "GND_3") (pintype "passive"))
      (node (ref "U10") (pin "7") (pinfunction "B_7") (pintype "passive"))
      (node (ref "U11") (pin "2") (pinfunction "GND_2") (pintype "passive"))
      (node (ref "U12") (pin "11") (pinfunction "GND_PA_11") (pintype "passive"))
      (node (ref "U12") (pin "21") (pinfunction "EP_21") (pintype "passive"))
      (node (ref "U13") (pin "2") (pinfunction "GND_2") (pintype "passive"))
      (node (ref "U14") (pin "2") (pinfunction "GND_2") (pintype "passive"))
      (node (ref "U14") (pin "7") (pinfunction "GND_7") (pintype "passive"))
      (node (ref "U14") (pin "9") (pinfunction "EP_9") (pintype "passive"))
      (node (ref "U15") (pin "5") (pinfunction "POUT_5") (pintype "passive"))
      (node (ref "U16") (pin "2") (pinfunction "GND_2") (pintype "passive"))
      (node (ref "U17") (pin "1") (pinfunction "GND_1") (pintype "passive"))
      (node (ref "U17") (pin "2") (pinfunction "GND_2") (pintype "passive"))
      (node (ref "U17") (pin "5") (pinfunction "GND_5") (pintype "passive"))
      (node (ref "U18") (pin "1") (pinfunction "GND_1") (pintype "passive"))
      (node (ref "U18") (pin "3") (pinfunction "GND_3") (pintype "passive"))
      (node (ref "U18") (pin "4") (pinfunction "GND_4") (pintype "passive"))
      (node (ref "U18") (pin "5") (pinfunction "GND_5") (pintype "passive"))
      (node (ref "U18") (pin "7") (pinfunction "GND_7") (pintype "passive"))
      (node (ref "U18") (pin "8") (pinfunction "GND_8") (pintype "passive"))
      (node (ref "U7") (pin "2") (pinfunction "GND_2") (pintype "passive"))
      (node (ref "U8") (pin "2") (pinfunction "GND_2") (pintype "passive"))
      (node (ref "U9") (pin "4") (pinfunction "GND_4") (pintype "passive"))
    )
    (net (code "31") (name "Net-(C39-Pad1)") (class "Default")
      (node (ref "C39") (pin "1") (pinfunction "1_1") (pintype "passive"))
      (node (ref "C40") (pin "2") (pinfunction "2_2") (pintype "passive"))
      (node (ref "C45") (pin "2") (pinfunction "2_2") (pintype "passive"))
      (node (ref "L10") (pin "1") (pinfunction "1_1") (pintype "passive"))
    )
    (net (code "32") (name "Net-(C39-Pad2)") (class "Default")
      (node (ref "C39") (pin "2") (pinfunction "2_2") (pintype "passive"))
      (node (ref "L3") (pin "1") (pinfunction "1_1") (pintype "passive"))
    )
    (net (code "33") (name "Net-(C43-Pad2)") (class "Default")
      (node (ref "C43") (pin "2") (pinfunction "2_2") (pintype "passive"))
      (node (ref "L8") (pin "1") (pinfunction "1_1") (pintype "passive"))
      (node (ref "L9") (pin "2") (pinfunction "2_2") (pintype "passive"))
    )
    (net (code "34") (name "Net-(C44-Pad2)") (class "Default")
      (node (ref "C44") (pin "2") (pinfunction "2_2") (pintype "passive"))
      (node (ref "L10") (pin "2") (pinfunction "2_2") (pintype "passive"))
      (node (ref "L3") (pin "2") (pinfunction "2_2") (pintype "passive"))
      (node (ref "L9") (pin "1") (pinfunction "1_1") (pintype "passive"))
    )
    (net (code "35") (name "Net-(C49-Pad1)") (class "Default")
      (node (ref "C49") (pin "1") (pinfunction "1_1") (pintype "passive"))
      (node (ref "C50") (pin "2") (pinfunction "2_2") (pintype "passive"))
      (node (ref "L12") (pin "1") (pinfunction "1_1") (pintype "passive"))
    )
    (net (code "36") (name "Net-(C52-Pad1)") (class "Default")
      (node (ref "C52") (pin "1") (pinfunction "1_1") (pintype "passive"))
      (node (ref "L15") (pin "1") (pinfunction "1_1") (pintype "passive"))
    )
    (net (code "37") (name "Net-(C55-Pad1)") (class "Default")
      (node (ref "C55") (pin "1") (pinfunction "1_1") (pintype "passive"))
      (node (ref "R21") (pin "1") (pinfunction "1_1") (pintype "passive"))
    )
    (net (code "38") (name "Net-(L5-Pad1)") (class "Default")
      (node (ref "L5") (pin "1") (pinfunction "1_1") (pintype "passive"))
      (node (ref "L6") (pin "2") (pinfunction "2_2") (pintype "passive"))
    )
    (net (code "39") (name "Net-(U10-W)") (class "Default")
      (node (ref "U10") (pin "1") (pinfunction "W_1") (pintype "passive"))
      (node (ref "U9") (pin "5") (pinfunction "TRIM_5") (pintype "passive"))
    )
    (net (code "40") (name "Net-(U11-BYPASS)") (class "Default")
      (node (ref "C24") (pin "2") (pinfunction "2_2") (pintype "passive"))
      (node (ref "U11") (pin "4") (pinfunction "BYPASS_4") (pintype "passive"))
    )
    (net (code "41") (name "Net-(U12-RF_N)") (class "Default")
      (node (ref "C53") (pin "2") (pinfunction "2_2") (pintype "passive"))
      (node (ref "L12") (pin "2") (pinfunction "2_2") (pintype "passive"))
      (node (ref "L13") (pin "1") (pinfunction "1_1") (pintype "passive"))
      (node (ref "U12") (pin "10") (pinfunction "RF_N_10") (pintype "passive"))
    )
    (net (code "42") (name "Net-(U12-RF_P)") (class "Default")
      (node (ref "C49") (pin "2") (pinfunction "2_2") (pintype "passive"))
      (node (ref "C52") (pin "2") (pinfunction "2_2") (pintype "passive"))
      (node (ref "L13") (pin "2") (pinfunction "2_2") (pintype "passive"))
      (node (ref "U12") (pin "9") (pinfunction "RF_P_9") (pintype "passive"))
    )
    (net (code "43") (name "Net-(U12-SMPS_Ext1)") (class "Default")
      (node (ref "L5") (pin "2") (pinfunction "2_2") (pintype "passive"))
      (node (ref "U12") (pin "14") (pinfunction "SMPS_Ext1_14") (pintype "passive"))
    )
    (net (code "44") (name "Net-(U12-SMPS_Ext2)") (class "Default")
      (node (ref "C25") (pin "2") (pinfunction "2_2") (pintype "passive"))
      (node (ref "C28") (pin "2") (pinfunction "2_2") (pintype "passive"))
      (node (ref "C35") (pin "1") (pinfunction "1_1") (pintype "passive"))
      (node (ref "L6") (pin "1") (pinfunction "1_1") (pintype "passive"))
      (node (ref "R18") (pin "2") (pinfunction "2_2") (pintype "passive"))
      (node (ref "U12") (pin "13") (pinfunction "SMPS_Ext2_13") (pintype "passive"))
    )
    (net (code "45") (name "Net-(U12-TX)") (class "Default")
      (node (ref "C42") (pin "2") (pinfunction "2_2") (pintype "passive"))
      (node (ref "L4") (pin "2") (pinfunction "2_2") (pintype "passive"))
      (node (ref "L8") (pin "2") (pinfunction "2_2") (pintype "passive"))
      (node (ref "U12") (pin "12") (pinfunction "TX_12") (pintype "passive"))
    )
    (net (code "46") (name "Net-(U12-VREG)") (class "Default")
      (node (ref "C26") (pin "1") (pinfunction "1_1") (pintype "passive"))
      (node (ref "C27") (pin "1") (pinfunction "1_1") (pintype "passive"))
      (node (ref "U12") (pin "17") (pinfunction "VREG_17") (pintype "passive"))
    )
    (net (code "47") (name "Net-(U12-XIN)") (class "Default")
      (node (ref "C56") (pin "1") (pinfunction "1_1") (pintype "passive"))
      (node (ref "U12") (pin "7") (pinfunction "XIN_7") (pintype "passive"))
    )
    (net (code "48") (name "Net-(U14-ACG)") (class "Default")
      (node (ref "C46") (pin "2") (pinfunction "2_2") (pintype "passive"))
      (node (ref "U14") (pin "4") (pinfunction "ACG_4") (pintype "passive"))
    )
    (net (code "49") (name "Net-(U14-RFC)") (class "Default")
      (node (ref "C36") (pin "1") (pinfunction "1_1") (pintype "passive"))
      (node (ref "C38") (pin "1") (pinfunction "1_1") (pintype "passive"))
      (node (ref "L2") (pin "1") (pinfunction "1_1") (pintype "passive"))
      (node (ref "L7") (pin "2") (pinfunction "2_2") (pintype "passive"))
      (node (ref "U14") (pin "8") (pinfunction "RFC_8") (pintype "passive"))
    )
    (net (code "50") (name "Net-(U14-RX)") (class "Default")
      (node (ref "C41") (pin "1") (pinfunction "1_1") (pintype "passive"))
      (node (ref "C47") (pin "2") (pinfunction "2_2") (pintype "passive"))
      (node (ref "L7") (pin "1") (pinfunction "1_1") (pintype "passive"))
      (node (ref "U14") (pin "5") (pinfunction "RX_5") (pintype "passive"))
    )
    (net (code "51") (name "Net-(U14-TX)") (class "Default")
      (node (ref "C37") (pin "2") (pinfunction "2_2") (pintype "passive"))
      (node (ref "L2") (pin "2") (pinfunction "2_2") (pintype "passive"))
      (node (ref "U14") (pin "1") (pinfunction "TX_1") (pintype "passive"))
    )
    (net (code "52") (name "Net-(U15-VDD)") (class "Default")
      (node (ref "C31") (pin "2") (pinfunction "2_2") (pintype "passive"))
      (node (ref "C32") (pin "2") (pinfunction "2_2") (pintype "passive"))
      (node (ref "L1") (pin "2") (pinfunction "2_2") (pintype "passive"))
      (node (ref "U15") (pin "3") (pinfunction "VDD_3") (pintype "passive"))
    )
    (net (code "53") (name "Net-(U16-OUT)") (class "Default")
      (node (ref "C56") (pin "2") (pinfunction "2_2") (pintype "passive"))
      (node (ref "U16") (pin "3") (pinfunction "OUT_3") (pintype "passive"))
    )
    (net (code "54") (name "Net-(U17-BIAS)") (class "Default")
      (node (ref "C55") (pin "2") (pinfunction "2_2") (pintype "passive"))
      (node (ref "L14") (pin "2") (pinfunction "2_2") (pintype "passive"))
      (node (ref "R20") (pin "1") (pinfunction "1_1") (pintype "passive"))
      (node (ref "U17") (pin "4") (pinfunction "BIAS_4") (pintype "passive"))
    )
    (net (code "55") (name "Net-(U18-RF_IN)") (class "Default")
      (node (ref "C41") (pin "2") (pinfunction "2_2") (pintype "passive"))
      (node (ref "U18") (pin "2") (pinfunction "RF_IN_2") (pintype "passive"))
    )
    (net (code "56") (name "Net-(U18-RF_OUT)") (class "Default")
      (node (ref "C51") (pin "1") (pinfunction "1_1") (pintype "passive"))
      (node (ref "U18") (pin "6") (pinfunction "RF_OUT_6") (pintype "passive"))
    )
    (net (code "57") (name "VBAT") (class "Default")
      (node (ref "C18") (pin "2") (pinfunction "2_2") (pintype "passive"))
      (node (ref "U7") (pin "1") (pinfunction "IN_1") (pintype "passive"))
      (node (ref "U9") (pin "2") (pinfunction "VIN_2") (pintype "passive"))
    )
    (net (code "58") (name "VDD_PA") (class "Default")
      (node (ref "L1") (pin "1") (pinfunction "1_1") (pintype "passive"))
      (node (ref "U9") (pin "6") (pinfunction "VOUT_6") (pintype "passive"))
    )
    (net (code "59") (name "unconnected-(U7-NC-Pad4)") (class "Default")
      (node (ref "U7") (pin "4") (pinfunction "NC_4") (pintype "passive"))
    )
    (net (code "60") (name "unconnected-(U8-NC-Pad4)") (class "Default")
      (node (ref "U8") (pin "4") (pinfunction "NC_4") (pintype "passive"))
    )
    (net (code "61") (name "unconnected-(U9-+SENSE-Pad7)") (class "Default")
      (node (ref "U9") (pin "7") (pinfunction "+SENSE_7") (pintype "passive"))
    )
    (net (code "62") (name "unconnected-(U9--SENSE-Pad8)") (class "Default")
      (node (ref "U9") (pin "8") (pinfunction "-SENSE_8") (pintype "passive"))
    )
    (net (code "63") (name "unconnected-(U9-PGOOD-Pad9)") (class "Default")
      (node (ref "U9") (pin "9") (pinfunction "PGOOD_9") (pintype "passive"))
    )
    (net (code "64") (name "unconnected-(U9-SEQ-Pad3)") (class "Default")
      (node (ref "U9") (pin "3") (pinfunction "SEQ_3") (pintype "passive"))
    )
    (net (code "65") (name "unconnected-(U9-SYNC-Pad10)") (class "Default")
      (node (ref "U9") (pin "10") (pinfunction "SYNC_10") (pintype "passive"))
    )
    (net (code "66") (name "unconnected-(U10-A-Pad8)") (class "Default")
      (node (ref "U10") (pin "8") (pinfunction "A_8") (pintype "passive"))
    )
    (net (code "67") (name "unconnected-(U12-XOUT-Pad6)") (class "Default")
      (node (ref "U12") (pin "6") (pinfunction "XOUT_6") (pintype "passive"))
    )
    (net (code "68") (name "unconnected-(U16-NC-Pad1)") (class "Default")
      (node (ref "U16") (pin "1") (pinfunction "NC_1") (pintype "passive"))
    )
  )
)
